# battery_display.net
KiCad netlist of a schematic drawn in EAGLE
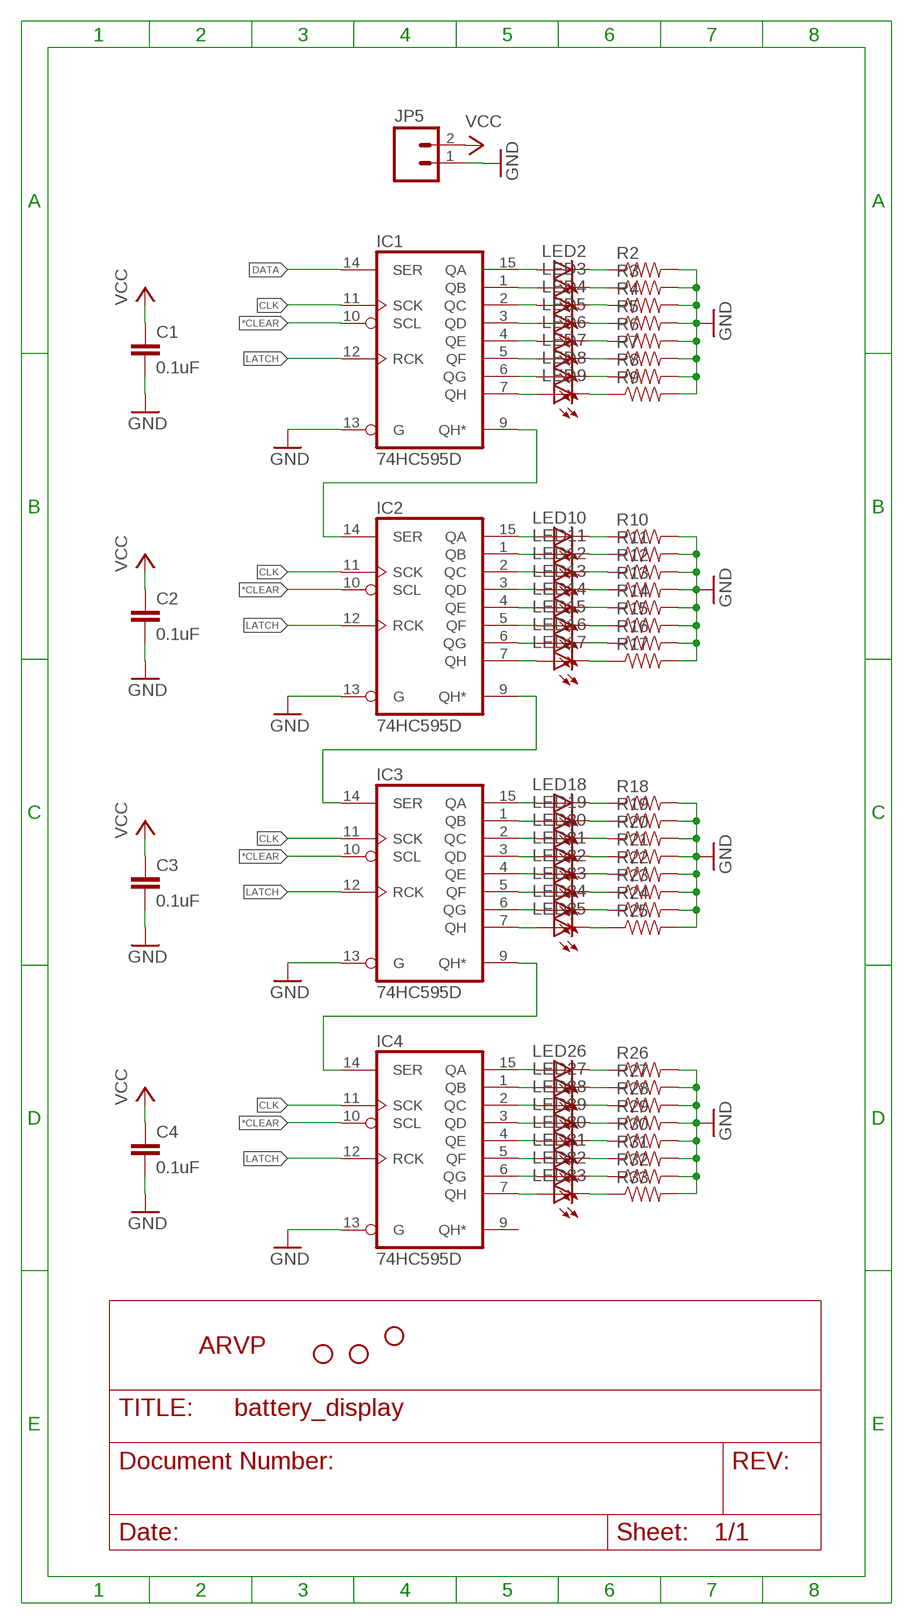
[diagram p0: schematic, sheet 1]

(export (version "E")
  (design (tool "Eeschema 10.0.6"))
  (components
    (comp (ref "C1")
      (value "0.1uF")
      (footprint "eagle-import:1206")
      (libsource (lib "eagle-import") (part "CAP1206"))
    )
    (comp (ref "C2")
      (value "0.1uF")
      (footprint "eagle-import:1206")
      (libsource (lib "eagle-import") (part "CAP1206"))
    )
    (comp (ref "C3")
      (value "0.1uF")
      (footprint "eagle-import:1206")
      (libsource (lib "eagle-import") (part "CAP1206"))
    )
    (comp (ref "C4")
      (value "0.1uF")
      (footprint "eagle-import:1206")
      (libsource (lib "eagle-import") (part "CAP1206"))
    )
    (comp (ref "IC1")
      (value "74HC595D")
      (footprint "eagle-import:SO16")
      (libsource (lib "eagle-import") (part "74595DHC"))
    )
    (comp (ref "IC2")
      (value "74HC595D")
      (footprint "eagle-import:SO16")
      (libsource (lib "eagle-import") (part "74595DHC"))
    )
    (comp (ref "IC3")
      (value "74HC595D")
      (footprint "eagle-import:SO16")
      (libsource (lib "eagle-import") (part "74595DHC"))
    )
    (comp (ref "IC4")
      (value "74HC595D")
      (footprint "eagle-import:SO16")
      (libsource (lib "eagle-import") (part "74595DHC"))
    )
    (comp (ref "JP2")
      (value "STAND-OFF")
      (footprint "eagle-import:STAND-OFF")
      (libsource (lib "eagle-import") (part "STAND-OFF"))
    )
    (comp (ref "JP3")
      (value "STAND-OFF")
      (footprint "eagle-import:STAND-OFF")
      (libsource (lib "eagle-import") (part "STAND-OFF"))
    )
    (comp (ref "JP4")
      (value "STAND-OFF")
      (footprint "eagle-import:STAND-OFF")
      (libsource (lib "eagle-import") (part "STAND-OFF"))
    )
    (comp (ref "JP5")
      (value "M02POLAR_LOCK")
      (footprint "eagle-import:MOLEX-1X2_LOCK")
      (libsource (lib "eagle-import") (part "M02POLAR_LOCK"))
    )
    (comp (ref "LED2")
      (value "LED1206")
      (footprint "eagle-import:LED-1206")
      (libsource (lib "eagle-import") (part "LED1206"))
    )
    (comp (ref "LED3")
      (value "LED1206")
      (footprint "eagle-import:LED-1206")
      (libsource (lib "eagle-import") (part "LED1206"))
    )
    (comp (ref "LED4")
      (value "LED1206")
      (footprint "eagle-import:LED-1206")
      (libsource (lib "eagle-import") (part "LED1206"))
    )
    (comp (ref "LED5")
      (value "LED1206")
      (footprint "eagle-import:LED-1206")
      (libsource (lib "eagle-import") (part "LED1206"))
    )
    (comp (ref "LED6")
      (value "LED1206")
      (footprint "eagle-import:LED-1206")
      (libsource (lib "eagle-import") (part "LED1206"))
    )
    (comp (ref "LED7")
      (value "LED1206")
      (footprint "eagle-import:LED-1206")
      (libsource (lib "eagle-import") (part "LED1206"))
    )
    (comp (ref "LED8")
      (value "LED1206")
      (footprint "eagle-import:LED-1206")
      (libsource (lib "eagle-import") (part "LED1206"))
    )
    (comp (ref "LED9")
      (value "LED1206")
      (footprint "eagle-import:LED-1206")
      (libsource (lib "eagle-import") (part "LED1206"))
    )
    (comp (ref "LED10")
      (value "LED1206")
      (footprint "eagle-import:LED-1206")
      (libsource (lib "eagle-import") (part "LED1206"))
    )
    (comp (ref "LED11")
      (value "LED1206")
      (footprint "eagle-import:LED-1206")
      (libsource (lib "eagle-import") (part "LED1206"))
    )
    (comp (ref "LED12")
      (value "LED1206")
      (footprint "eagle-import:LED-1206")
      (libsource (lib "eagle-import") (part "LED1206"))
    )
    (comp (ref "LED13")
      (value "LED1206")
      (footprint "eagle-import:LED-1206")
      (libsource (lib "eagle-import") (part "LED1206"))
    )
    (comp (ref "LED14")
      (value "LED1206")
      (footprint "eagle-import:LED-1206")
      (libsource (lib "eagle-import") (part "LED1206"))
    )
    (comp (ref "LED15")
      (value "LED1206")
      (footprint "eagle-import:LED-1206")
      (libsource (lib "eagle-import") (part "LED1206"))
    )
    (comp (ref "LED16")
      (value "LED1206")
      (footprint "eagle-import:LED-1206")
      (libsource (lib "eagle-import") (part "LED1206"))
    )
    (comp (ref "LED17")
      (value "LED1206")
      (footprint "eagle-import:LED-1206")
      (libsource (lib "eagle-import") (part "LED1206"))
    )
    (comp (ref "LED18")
      (value "LED1206")
      (footprint "eagle-import:LED-1206")
      (libsource (lib "eagle-import") (part "LED1206"))
    )
    (comp (ref "LED19")
      (value "LED1206")
      (footprint "eagle-import:LED-1206")
      (libsource (lib "eagle-import") (part "LED1206"))
    )
    (comp (ref "LED20")
      (value "LED1206")
      (footprint "eagle-import:LED-1206")
      (libsource (lib "eagle-import") (part "LED1206"))
    )
    (comp (ref "LED21")
      (value "LED1206")
      (footprint "eagle-import:LED-1206")
      (libsource (lib "eagle-import") (part "LED1206"))
    )
    (comp (ref "LED22")
      (value "LED1206")
      (footprint "eagle-import:LED-1206")
      (libsource (lib "eagle-import") (part "LED1206"))
    )
    (comp (ref "LED23")
      (value "LED1206")
      (footprint "eagle-import:LED-1206")
      (libsource (lib "eagle-import") (part "LED1206"))
    )
    (comp (ref "LED24")
      (value "LED1206")
      (footprint "eagle-import:LED-1206")
      (libsource (lib "eagle-import") (part "LED1206"))
    )
    (comp (ref "LED25")
      (value "LED1206")
      (footprint "eagle-import:LED-1206")
      (libsource (lib "eagle-import") (part "LED1206"))
    )
    (comp (ref "LED26")
      (value "LED1206")
      (footprint "eagle-import:LED-1206")
      (libsource (lib "eagle-import") (part "LED1206"))
    )
    (comp (ref "LED27")
      (value "LED1206")
      (footprint "eagle-import:LED-1206")
      (libsource (lib "eagle-import") (part "LED1206"))
    )
    (comp (ref "LED28")
      (value "LED1206")
      (footprint "eagle-import:LED-1206")
      (libsource (lib "eagle-import") (part "LED1206"))
    )
    (comp (ref "LED29")
      (value "LED1206")
      (footprint "eagle-import:LED-1206")
      (libsource (lib "eagle-import") (part "LED1206"))
    )
    (comp (ref "LED30")
      (value "LED1206")
      (footprint "eagle-import:LED-1206")
      (libsource (lib "eagle-import") (part "LED1206"))
    )
    (comp (ref "LED31")
      (value "LED1206")
      (footprint "eagle-import:LED-1206")
      (libsource (lib "eagle-import") (part "LED1206"))
    )
    (comp (ref "LED32")
      (value "LED1206")
      (footprint "eagle-import:LED-1206")
      (libsource (lib "eagle-import") (part "LED1206"))
    )
    (comp (ref "LED33")
      (value "LED1206")
      (footprint "eagle-import:LED-1206")
      (libsource (lib "eagle-import") (part "LED1206"))
    )
    (comp (ref "R2")
      (value "RESISTOR1206")
      (footprint "eagle-import:1206")
      (libsource (lib "eagle-import") (part "RESISTOR1206"))
    )
    (comp (ref "R3")
      (value "RESISTOR1206")
      (footprint "eagle-import:1206")
      (libsource (lib "eagle-import") (part "RESISTOR1206"))
    )
    (comp (ref "R4")
      (value "RESISTOR1206")
      (footprint "eagle-import:1206")
      (libsource (lib "eagle-import") (part "RESISTOR1206"))
    )
    (comp (ref "R5")
      (value "RESISTOR1206")
      (footprint "eagle-import:1206")
      (libsource (lib "eagle-import") (part "RESISTOR1206"))
    )
    (comp (ref "R6")
      (value "RESISTOR1206")
      (footprint "eagle-import:1206")
      (libsource (lib "eagle-import") (part "RESISTOR1206"))
    )
    (comp (ref "R7")
      (value "RESISTOR1206")
      (footprint "eagle-import:1206")
      (libsource (lib "eagle-import") (part "RESISTOR1206"))
    )
    (comp (ref "R8")
      (value "RESISTOR1206")
      (footprint "eagle-import:1206")
      (libsource (lib "eagle-import") (part "RESISTOR1206"))
    )
    (comp (ref "R9")
      (value "RESISTOR1206")
      (footprint "eagle-import:1206")
      (libsource (lib "eagle-import") (part "RESISTOR1206"))
    )
    (comp (ref "R10")
      (value "RESISTOR1206")
      (footprint "eagle-import:1206")
      (libsource (lib "eagle-import") (part "RESISTOR1206"))
    )
    (comp (ref "R11")
      (value "RESISTOR1206")
      (footprint "eagle-import:1206")
      (libsource (lib "eagle-import") (part "RESISTOR1206"))
    )
    (comp (ref "R12")
      (value "RESISTOR1206")
      (footprint "eagle-import:1206")
      (libsource (lib "eagle-import") (part "RESISTOR1206"))
    )
    (comp (ref "R13")
      (value "RESISTOR1206")
      (footprint "eagle-import:1206")
      (libsource (lib "eagle-import") (part "RESISTOR1206"))
    )
    (comp (ref "R14")
      (value "RESISTOR1206")
      (footprint "eagle-import:1206")
      (libsource (lib "eagle-import") (part "RESISTOR1206"))
    )
    (comp (ref "R15")
      (value "RESISTOR1206")
      (footprint "eagle-import:1206")
      (libsource (lib "eagle-import") (part "RESISTOR1206"))
    )
    (comp (ref "R16")
      (value "RESISTOR1206")
      (footprint "eagle-import:1206")
      (libsource (lib "eagle-import") (part "RESISTOR1206"))
    )
    (comp (ref "R17")
      (value "RESISTOR1206")
      (footprint "eagle-import:1206")
      (libsource (lib "eagle-import") (part "RESISTOR1206"))
    )
    (comp (ref "R18")
      (value "RESISTOR1206")
      (footprint "eagle-import:1206")
      (libsource (lib "eagle-import") (part "RESISTOR1206"))
    )
    (comp (ref "R19")
      (value "RESISTOR1206")
      (footprint "eagle-import:1206")
      (libsource (lib "eagle-import") (part "RESISTOR1206"))
    )
    (comp (ref "R20")
      (value "RESISTOR1206")
      (footprint "eagle-import:1206")
      (libsource (lib "eagle-import") (part "RESISTOR1206"))
    )
    (comp (ref "R21")
      (value "RESISTOR1206")
      (footprint "eagle-import:1206")
      (libsource (lib "eagle-import") (part "RESISTOR1206"))
    )
    (comp (ref "R22")
      (value "RESISTOR1206")
      (footprint "eagle-import:1206")
      (libsource (lib "eagle-import") (part "RESISTOR1206"))
    )
    (comp (ref "R23")
      (value "RESISTOR1206")
      (footprint "eagle-import:1206")
      (libsource (lib "eagle-import") (part "RESISTOR1206"))
    )
    (comp (ref "R24")
      (value "RESISTOR1206")
      (footprint "eagle-import:1206")
      (libsource (lib "eagle-import") (part "RESISTOR1206"))
    )
    (comp (ref "R25")
      (value "RESISTOR1206")
      (footprint "eagle-import:1206")
      (libsource (lib "eagle-import") (part "RESISTOR1206"))
    )
    (comp (ref "R26")
      (value "RESISTOR1206")
      (footprint "eagle-import:1206")
      (libsource (lib "eagle-import") (part "RESISTOR1206"))
    )
    (comp (ref "R27")
      (value "RESISTOR1206")
      (footprint "eagle-import:1206")
      (libsource (lib "eagle-import") (part "RESISTOR1206"))
    )
    (comp (ref "R28")
      (value "RESISTOR1206")
      (footprint "eagle-import:1206")
      (libsource (lib "eagle-import") (part "RESISTOR1206"))
    )
    (comp (ref "R29")
      (value "RESISTOR1206")
      (footprint "eagle-import:1206")
      (libsource (lib "eagle-import") (part "RESISTOR1206"))
    )
    (comp (ref "R30")
      (value "RESISTOR1206")
      (footprint "eagle-import:1206")
      (libsource (lib "eagle-import") (part "RESISTOR1206"))
    )
    (comp (ref "R31")
      (value "RESISTOR1206")
      (footprint "eagle-import:1206")
      (libsource (lib "eagle-import") (part "RESISTOR1206"))
    )
    (comp (ref "R32")
      (value "RESISTOR1206")
      (footprint "eagle-import:1206")
      (libsource (lib "eagle-import") (part "RESISTOR1206"))
    )
    (comp (ref "R33")
      (value "RESISTOR1206")
      (footprint "eagle-import:1206")
      (libsource (lib "eagle-import") (part "RESISTOR1206"))
    )
    (comp (ref "U$2")
      (value "ARVP_LOGO")
      (footprint "eagle-import:ARVP")
      (libsource (lib "eagle-import") (part "ARVP_LOGO"))
    )
  )
  (nets
    (net (code "1") (name "*CLEAR") (class "Default")
      (node (ref "IC1") (pin "10") (pinfunction "SCL_10") (pintype "input"))
      (node (ref "IC2") (pin "10") (pinfunction "SCL_10") (pintype "input"))
      (node (ref "IC3") (pin "10") (pinfunction "SCL_10") (pintype "input"))
      (node (ref "IC4") (pin "10") (pinfunction "SCL_10") (pintype "input"))
    )
    (net (code "2") (name "CLK") (class "Default")
      (node (ref "IC1") (pin "11") (pinfunction "SCK_11") (pintype "input"))
      (node (ref "IC2") (pin "11") (pinfunction "SCK_11") (pintype "input"))
      (node (ref "IC3") (pin "11") (pinfunction "SCK_11") (pintype "input"))
      (node (ref "IC4") (pin "11") (pinfunction "SCK_11") (pintype "input"))
    )
    (net (code "3") (name "DATA") (class "Default")
      (node (ref "IC1") (pin "14") (pinfunction "SER_14") (pintype "input"))
    )
    (net (code "4") (name "GND") (class "Default")
      (node (ref "C1") (pin "2") (pinfunction "2_2") (pintype "passive"))
      (node (ref "C2") (pin "2") (pinfunction "2_2") (pintype "passive"))
      (node (ref "C3") (pin "2") (pinfunction "2_2") (pintype "passive"))
      (node (ref "C4") (pin "2") (pinfunction "2_2") (pintype "passive"))
      (node (ref "IC1") (pin "13") (pinfunction "G_13") (pintype "input"))
      (node (ref "IC2") (pin "13") (pinfunction "G_13") (pintype "input"))
      (node (ref "IC3") (pin "13") (pinfunction "G_13") (pintype "input"))
      (node (ref "IC4") (pin "13") (pinfunction "G_13") (pintype "input"))
      (node (ref "JP5") (pin "1") (pinfunction "1_1") (pintype "passive"))
      (node (ref "R10") (pin "2") (pinfunction "2_2") (pintype "passive"))
      (node (ref "R11") (pin "2") (pinfunction "2_2") (pintype "passive"))
      (node (ref "R12") (pin "2") (pinfunction "2_2") (pintype "passive"))
      (node (ref "R13") (pin "2") (pinfunction "2_2") (pintype "passive"))
      (node (ref "R14") (pin "2") (pinfunction "2_2") (pintype "passive"))
      (node (ref "R15") (pin "2") (pinfunction "2_2") (pintype "passive"))
      (node (ref "R16") (pin "2") (pinfunction "2_2") (pintype "passive"))
      (node (ref "R17") (pin "2") (pinfunction "2_2") (pintype "passive"))
      (node (ref "R18") (pin "2") (pinfunction "2_2") (pintype "passive"))
      (node (ref "R19") (pin "2") (pinfunction "2_2") (pintype "passive"))
      (node (ref "R2") (pin "2") (pinfunction "2_2") (pintype "passive"))
      (node (ref "R20") (pin "2") (pinfunction "2_2") (pintype "passive"))
      (node (ref "R21") (pin "2") (pinfunction "2_2") (pintype "passive"))
      (node (ref "R22") (pin "2") (pinfunction "2_2") (pintype "passive"))
      (node (ref "R23") (pin "2") (pinfunction "2_2") (pintype "passive"))
      (node (ref "R24") (pin "2") (pinfunction "2_2") (pintype "passive"))
      (node (ref "R25") (pin "2") (pinfunction "2_2") (pintype "passive"))
      (node (ref "R26") (pin "2") (pinfunction "2_2") (pintype "passive"))
      (node (ref "R27") (pin "2") (pinfunction "2_2") (pintype "passive"))
      (node (ref "R28") (pin "2") (pinfunction "2_2") (pintype "passive"))
      (node (ref "R29") (pin "2") (pinfunction "2_2") (pintype "passive"))
      (node (ref "R3") (pin "2") (pinfunction "2_2") (pintype "passive"))
      (node (ref "R30") (pin "2") (pinfunction "2_2") (pintype "passive"))
      (node (ref "R31") (pin "2") (pinfunction "2_2") (pintype "passive"))
      (node (ref "R32") (pin "2") (pinfunction "2_2") (pintype "passive"))
      (node (ref "R33") (pin "2") (pinfunction "2_2") (pintype "passive"))
      (node (ref "R4") (pin "2") (pinfunction "2_2") (pintype "passive"))
      (node (ref "R5") (pin "2") (pinfunction "2_2") (pintype "passive"))
      (node (ref "R6") (pin "2") (pinfunction "2_2") (pintype "passive"))
      (node (ref "R7") (pin "2") (pinfunction "2_2") (pintype "passive"))
      (node (ref "R8") (pin "2") (pinfunction "2_2") (pintype "passive"))
      (node (ref "R9") (pin "2") (pinfunction "2_2") (pintype "passive"))
    )
    (net (code "5") (name "LATCH") (class "Default")
      (node (ref "IC1") (pin "12") (pinfunction "RCK_12") (pintype "input"))
      (node (ref "IC2") (pin "12") (pinfunction "RCK_12") (pintype "input"))
      (node (ref "IC3") (pin "12") (pinfunction "RCK_12") (pintype "input"))
      (node (ref "IC4") (pin "12") (pinfunction "RCK_12") (pintype "input"))
    )
    (net (code "6") (name "Net-(IC1A-QA)") (class "Default")
      (node (ref "IC1") (pin "15") (pinfunction "QA_15") (pintype "tri_state"))
      (node (ref "LED2") (pin "A") (pinfunction "A_A") (pintype "passive"))
    )
    (net (code "7") (name "Net-(IC1A-QB)") (class "Default")
      (node (ref "IC1") (pin "1") (pinfunction "QB_1") (pintype "tri_state"))
      (node (ref "LED3") (pin "A") (pinfunction "A_A") (pintype "passive"))
    )
    (net (code "8") (name "Net-(IC1A-QC)") (class "Default")
      (node (ref "IC1") (pin "2") (pinfunction "QC_2") (pintype "tri_state"))
      (node (ref "LED4") (pin "A") (pinfunction "A_A") (pintype "passive"))
    )
    (net (code "9") (name "Net-(IC1A-QD)") (class "Default")
      (node (ref "IC1") (pin "3") (pinfunction "QD_3") (pintype "tri_state"))
      (node (ref "LED5") (pin "A") (pinfunction "A_A") (pintype "passive"))
    )
    (net (code "10") (name "Net-(IC1A-QE)") (class "Default")
      (node (ref "IC1") (pin "4") (pinfunction "QE_4") (pintype "tri_state"))
      (node (ref "LED6") (pin "A") (pinfunction "A_A") (pintype "passive"))
    )
    (net (code "11") (name "Net-(IC1A-QF)") (class "Default")
      (node (ref "IC1") (pin "5") (pinfunction "QF_5") (pintype "tri_state"))
      (node (ref "LED7") (pin "A") (pinfunction "A_A") (pintype "passive"))
    )
    (net (code "12") (name "Net-(IC1A-QG)") (class "Default")
      (node (ref "IC1") (pin "6") (pinfunction "QG_6") (pintype "tri_state"))
      (node (ref "LED8") (pin "A") (pinfunction "A_A") (pintype "passive"))
    )
    (net (code "13") (name "Net-(IC1A-QH)") (class "Default")
      (node (ref "IC1") (pin "7") (pinfunction "QH_7") (pintype "tri_state"))
      (node (ref "LED9") (pin "A") (pinfunction "A_A") (pintype "passive"))
    )
    (net (code "14") (name "Net-(IC1A-QH*)") (class "Default")
      (node (ref "IC1") (pin "9") (pinfunction "QH*_9") (pintype "tri_state"))
      (node (ref "IC2") (pin "14") (pinfunction "SER_14") (pintype "input"))
    )
    (net (code "15") (name "Net-(IC2A-QA)") (class "Default")
      (node (ref "IC2") (pin "15") (pinfunction "QA_15") (pintype "tri_state"))
      (node (ref "LED10") (pin "A") (pinfunction "A_A") (pintype "passive"))
    )
    (net (code "16") (name "Net-(IC2A-QB)") (class "Default")
      (node (ref "IC2") (pin "1") (pinfunction "QB_1") (pintype "tri_state"))
      (node (ref "LED11") (pin "A") (pinfunction "A_A") (pintype "passive"))
    )
    (net (code "17") (name "Net-(IC2A-QC)") (class "Default")
      (node (ref "IC2") (pin "2") (pinfunction "QC_2") (pintype "tri_state"))
      (node (ref "LED12") (pin "A") (pinfunction "A_A") (pintype "passive"))
    )
    (net (code "18") (name "Net-(IC2A-QD)") (class "Default")
      (node (ref "IC2") (pin "3") (pinfunction "QD_3") (pintype "tri_state"))
      (node (ref "LED13") (pin "A") (pinfunction "A_A") (pintype "passive"))
    )
    (net (code "19") (name "Net-(IC2A-QE)") (class "Default")
      (node (ref "IC2") (pin "4") (pinfunction "QE_4") (pintype "tri_state"))
      (node (ref "LED14") (pin "A") (pinfunction "A_A") (pintype "passive"))
    )
    (net (code "20") (name "Net-(IC2A-QF)") (class "Default")
      (node (ref "IC2") (pin "5") (pinfunction "QF_5") (pintype "tri_state"))
      (node (ref "LED15") (pin "A") (pinfunction "A_A") (pintype "passive"))
    )
    (net (code "21") (name "Net-(IC2A-QG)") (class "Default")
      (node (ref "IC2") (pin "6") (pinfunction "QG_6") (pintype "tri_state"))
      (node (ref "LED16") (pin "A") (pinfunction "A_A") (pintype "passive"))
    )
    (net (code "22") (name "Net-(IC2A-QH)") (class "Default")
      (node (ref "IC2") (pin "7") (pinfunction "QH_7") (pintype "tri_state"))
      (node (ref "LED17") (pin "A") (pinfunction "A_A") (pintype "passive"))
    )
    (net (code "23") (name "Net-(IC2A-QH*)") (class "Default")
      (node (ref "IC2") (pin "9") (pinfunction "QH*_9") (pintype "tri_state"))
      (node (ref "IC3") (pin "14") (pinfunction "SER_14") (pintype "input"))
    )
    (net (code "24") (name "Net-(IC3A-QA)") (class "Default")
      (node (ref "IC3") (pin "15") (pinfunction "QA_15") (pintype "tri_state"))
      (node (ref "LED18") (pin "A") (pinfunction "A_A") (pintype "passive"))
    )
    (net (code "25") (name "Net-(IC3A-QB)") (class "Default")
      (node (ref "IC3") (pin "1") (pinfunction "QB_1") (pintype "tri_state"))
      (node (ref "LED19") (pin "A") (pinfunction "A_A") (pintype "passive"))
    )
    (net (code "26") (name "Net-(IC3A-QC)") (class "Default")
      (node (ref "IC3") (pin "2") (pinfunction "QC_2") (pintype "tri_state"))
      (node (ref "LED20") (pin "A") (pinfunction "A_A") (pintype "passive"))
    )
    (net (code "27") (name "Net-(IC3A-QD)") (class "Default")
      (node (ref "IC3") (pin "3") (pinfunction "QD_3") (pintype "tri_state"))
      (node (ref "LED21") (pin "A") (pinfunction "A_A") (pintype "passive"))
    )
    (net (code "28") (name "Net-(IC3A-QE)") (class "Default")
      (node (ref "IC3") (pin "4") (pinfunction "QE_4") (pintype "tri_state"))
      (node (ref "LED22") (pin "A") (pinfunction "A_A") (pintype "passive"))
    )
    (net (code "29") (name "Net-(IC3A-QF)") (class "Default")
      (node (ref "IC3") (pin "5") (pinfunction "QF_5") (pintype "tri_state"))
      (node (ref "LED23") (pin "A") (pinfunction "A_A") (pintype "passive"))
    )
    (net (code "30") (name "Net-(IC3A-QG)") (class "Default")
      (node (ref "IC3") (pin "6") (pinfunction "QG_6") (pintype "tri_state"))
      (node (ref "LED24") (pin "A") (pinfunction "A_A") (pintype "passive"))
    )
    (net (code "31") (name "Net-(IC3A-QH)") (class "Default")
      (node (ref "IC3") (pin "7") (pinfunction "QH_7") (pintype "tri_state"))
      (node (ref "LED25") (pin "A") (pinfunction "A_A") (pintype "passive"))
    )
    (net (code "32") (name "Net-(IC3A-QH*)") (class "Default")
      (node (ref "IC3") (pin "9") (pinfunction "QH*_9") (pintype "tri_state"))
      (node (ref "IC4") (pin "14") (pinfunction "SER_14") (pintype "input"))
    )
    (net (code "33") (name "Net-(IC4A-QA)") (class "Default")
      (node (ref "IC4") (pin "15") (pinfunction "QA_15") (pintype "tri_state"))
      (node (ref "LED26") (pin "A") (pinfunction "A_A") (pintype "passive"))
    )
    (net (code "34") (name "Net-(IC4A-QB)") (class "Default")
      (node (ref "IC4") (pin "1") (pinfunction "QB_1") (pintype "tri_state"))
      (node (ref "LED27") (pin "A") (pinfunction "A_A") (pintype "passive"))
    )
    (net (code "35") (name "Net-(IC4A-QC)") (class "Default")
      (node (ref "IC4") (pin "2") (pinfunction "QC_2") (pintype "tri_state"))
      (node (ref "LED28") (pin "A") (pinfunction "A_A") (pintype "passive"))
    )
    (net (code "36") (name "Net-(IC4A-QD)") (class "Default")
      (node (ref "IC4") (pin "3") (pinfunction "QD_3") (pintype "tri_state"))
      (node (ref "LED29") (pin "A") (pinfunction "A_A") (pintype "passive"))
    )
    (net (code "37") (name "Net-(IC4A-QE)") (class "Default")
      (node (ref "IC4") (pin "4") (pinfunction "QE_4") (pintype "tri_state"))
      (node (ref "LED30") (pin "A") (pinfunction "A_A") (pintype "passive"))
    )
    (net (code "38") (name "Net-(IC4A-QF)") (class "Default")
      (node (ref "IC4") (pin "5") (pinfunction "QF_5") (pintype "tri_state"))
      (node (ref "LED31") (pin "A") (pinfunction "A_A") (pintype "passive"))
    )
    (net (code "39") (name "Net-(IC4A-QG)") (class "Default")
      (node (ref "IC4") (pin "6") (pinfunction "QG_6") (pintype "tri_state"))
      (node (ref "LED32") (pin "A") (pinfunction "A_A") (pintype "passive"))
    )
    (net (code "40") (name "Net-(IC4A-QH)") (class "Default")
      (node (ref "IC4") (pin "7") (pinfunction "QH_7") (pintype "tri_state"))
      (node (ref "LED33") (pin "A") (pinfunction "A_A") (pintype "passive"))
    )
    (net (code "41") (name "Net-(LED2-PadC)") (class "Default")
      (node (ref "LED2") (pin "C") (pinfunction "C_C") (pintype "passive"))
      (node (ref "R2") (pin "1") (pinfunction "1_1") (pintype "passive"))
    )
    (net (code "42") (name "Net-(LED3-PadC)") (class "Default")
      (node (ref "LED3") (pin "C") (pinfunction "C_C") (pintype "passive"))
      (node (ref "R3") (pin "1") (pinfunction "1_1") (pintype "passive"))
    )
    (net (code "43") (name "Net-(LED4-PadC)") (class "Default")
      (node (ref "LED4") (pin "C") (pinfunction "C_C") (pintype "passive"))
      (node (ref "R4") (pin "1") (pinfunction "1_1") (pintype "passive"))
    )
    (net (code "44") (name "Net-(LED5-PadC)") (class "Default")
      (node (ref "LED5") (pin "C") (pinfunction "C_C") (pintype "passive"))
      (node (ref "R5") (pin "1") (pinfunction "1_1") (pintype "passive"))
    )
    (net (code "45") (name "Net-(LED6-PadC)") (class "Default")
      (node (ref "LED6") (pin "C") (pinfunction "C_C") (pintype "passive"))
      (node (ref "R6") (pin "1") (pinfunction "1_1") (pintype "passive"))
    )
    (net (code "46") (name "Net-(LED7-PadC)") (class "Default")
      (node (ref "LED7") (pin "C") (pinfunction "C_C") (pintype "passive"))
      (node (ref "R7") (pin "1") (pinfunction "1_1") (pintype "passive"))
    )
    (net (code "47") (name "Net-(LED8-PadC)") (class "Default")
      (node (ref "LED8") (pin "C") (pinfunction "C_C") (pintype "passive"))
      (node (ref "R8") (pin "1") (pinfunction "1_1") (pintype "passive"))
    )
    (net (code "48") (name "Net-(LED9-PadC)") (class "Default")
      (node (ref "LED9") (pin "C") (pinfunction "C_C") (pintype "passive"))
      (node (ref "R9") (pin "1") (pinfunction "1_1") (pintype "passive"))
    )
    (net (code "49") (name "Net-(LED10-PadC)") (class "Default")
      (node (ref "LED10") (pin "C") (pinfunction "C_C") (pintype "passive"))
      (node (ref "R10") (pin "1") (pinfunction "1_1") (pintype "passive"))
    )
    (net (code "50") (name "Net-(LED11-PadC)") (class "Default")
      (node (ref "LED11") (pin "C") (pinfunction "C_C") (pintype "passive"))
      (node (ref "R11") (pin "1") (pinfunction "1_1") (pintype "passive"))
    )
    (net (code "51") (name "Net-(LED12-PadC)") (class "Default")
      (node (ref "LED12") (pin "C") (pinfunction "C_C") (pintype "passive"))
      (node (ref "R12") (pin "1") (pinfunction "1_1") (pintype "passive"))
    )
    (net (code "52") (name "Net-(LED13-PadC)") (class "Default")
      (node (ref "LED13") (pin "C") (pinfunction "C_C") (pintype "passive"))
      (node (ref "R13") (pin "1") (pinfunction "1_1") (pintype "passive"))
    )
    (net (code "53") (name "Net-(LED14-PadC)") (class "Default")
      (node (ref "LED14") (pin "C") (pinfunction "C_C") (pintype "passive"))
      (node (ref "R14") (pin "1") (pinfunction "1_1") (pintype "passive"))
    )
    (net (code "54") (name "Net-(LED15-PadC)") (class "Default")
      (node (ref "LED15") (pin "C") (pinfunction "C_C") (pintype "passive"))
      (node (ref "R15") (pin "1") (pinfunction "1_1") (pintype "passive"))
    )
    (net (code "55") (name "Net-(LED16-PadC)") (class "Default")
      (node (ref "LED16") (pin "C") (pinfunction "C_C") (pintype "passive"))
      (node (ref "R16") (pin "1") (pinfunction "1_1") (pintype "passive"))
    )
    (net (code "56") (name "Net-(LED17-PadC)") (class "Default")
      (node (ref "LED17") (pin "C") (pinfunction "C_C") (pintype "passive"))
      (node (ref "R17") (pin "1") (pinfunction "1_1") (pintype "passive"))
    )
    (net (code "57") (name "Net-(LED18-PadC)") (class "Default")
      (node (ref "LED18") (pin "C") (pinfunction "C_C") (pintype "passive"))
      (node (ref "R18") (pin "1") (pinfunction "1_1") (pintype "passive"))
    )
    (net (code "58") (name "Net-(LED19-PadC)") (class "Default")
      (node (ref "LED19") (pin "C") (pinfunction "C_C") (pintype "passive"))
      (node (ref "R19") (pin "1") (pinfunction "1_1") (pintype "passive"))
    )
    (net (code "59") (name "Net-(LED20-PadC)") (class "Default")
      (node (ref "LED20") (pin "C") (pinfunction "C_C") (pintype "passive"))
      (node (ref "R20") (pin "1") (pinfunction "1_1") (pintype "passive"))
    )
    (net (code "60") (name "Net-(LED21-PadC)") (class "Default")
      (node (ref "LED21") (pin "C") (pinfunction "C_C") (pintype "passive"))
      (node (ref "R21") (pin "1") (pinfunction "1_1") (pintype "passive"))
    )
    (net (code "61") (name "Net-(LED22-PadC)") (class "Default")
      (node (ref "LED22") (pin "C") (pinfunction "C_C") (pintype "passive"))
      (node (ref "R22") (pin "1") (pinfunction "1_1") (pintype "passive"))
    )
    (net (code "62") (name "Net-(LED23-PadC)") (class "Default")
      (node (ref "LED23") (pin "C") (pinfunction "C_C") (pintype "passive"))
      (node (ref "R23") (pin "1") (pinfunction "1_1") (pintype "passive"))
    )
    (net (code "63") (name "Net-(LED24-PadC)") (class "Default")
      (node (ref "LED24") (pin "C") (pinfunction "C_C") (pintype "passive"))
      (node (ref "R24") (pin "1") (pinfunction "1_1") (pintype "passive"))
    )
    (net (code "64") (name "Net-(LED25-PadC)") (class "Default")
      (node (ref "LED25") (pin "C") (pinfunction "C_C") (pintype "passive"))
      (node (ref "R25") (pin "1") (pinfunction "1_1") (pintype "passive"))
    )
    (net (code "65") (name "Net-(LED26-PadC)") (class "Default")
      (node (ref "LED26") (pin "C") (pinfunction "C_C") (pintype "passive"))
      (node (ref "R26") (pin "1") (pinfunction "1_1") (pintype "passive"))
    )
    (net (code "66") (name "Net-(LED27-PadC)") (class "Default")
      (node (ref "LED27") (pin "C") (pinfunction "C_C") (pintype "passive"))
      (node (ref "R27") (pin "1") (pinfunction "1_1") (pintype "passive"))
    )
    (net (code "67") (name "Net-(LED28-PadC)") (class "Default")
      (node (ref "LED28") (pin "C") (pinfunction "C_C") (pintype "passive"))
      (node (ref "R28") (pin "1") (pinfunction "1_1") (pintype "passive"))
    )
    (net (code "68") (name "Net-(LED29-PadC)") (class "Default")
      (node (ref "LED29") (pin "C") (pinfunction "C_C") (pintype "passive"))
      (node (ref "R29") (pin "1") (pinfunction "1_1") (pintype "passive"))
    )
    (net (code "69") (name "Net-(LED30-PadC)") (class "Default")
      (node (ref "LED30") (pin "C") (pinfunction "C_C") (pintype "passive"))
      (node (ref "R30") (pin "1") (pinfunction "1_1") (pintype "passive"))
    )
    (net (code "70") (name "Net-(LED31-PadC)") (class "Default")
      (node (ref "LED31") (pin "C") (pinfunction "C_C") (pintype "passive"))
      (node (ref "R31") (pin "1") (pinfunction "1_1") (pintype "passive"))
    )
    (net (code "71") (name "Net-(LED32-PadC)") (class "Default")
      (node (ref "LED32") (pin "C") (pinfunction "C_C") (pintype "passive"))
      (node (ref "R32") (pin "1") (pinfunction "1_1") (pintype "passive"))
    )
    (net (code "72") (name "Net-(LED33-PadC)") (class "Default")
      (node (ref "LED33") (pin "C") (pinfunction "C_C") (pintype "passive"))
      (node (ref "R33") (pin "1") (pinfunction "1_1") (pintype "passive"))
    )
    (net (code "73") (name "VCC") (class "Default")
      (node (ref "C1") (pin "1") (pinfunction "1_1") (pintype "passive"))
      (node (ref "C2") (pin "1") (pinfunction "1_1") (pintype "passive"))
      (node (ref "C3") (pin "1") (pinfunction "1_1") (pintype "passive"))
      (node (ref "C4") (pin "1") (pinfunction "1_1") (pintype "passive"))
      (node (ref "JP5") (pin "2") (pinfunction "2_2") (pintype "passive"))
    )
    (net (code "74") (name "unconnected-(IC4A-QH*-Pad9)") (class "Default")
      (node (ref "IC4") (pin "9") (pinfunction "QH*_9") (pintype "tri_state"))
    )
  )
)
